# ISRelayV13.net
KiCad netlist of a schematic drawn in EAGLE
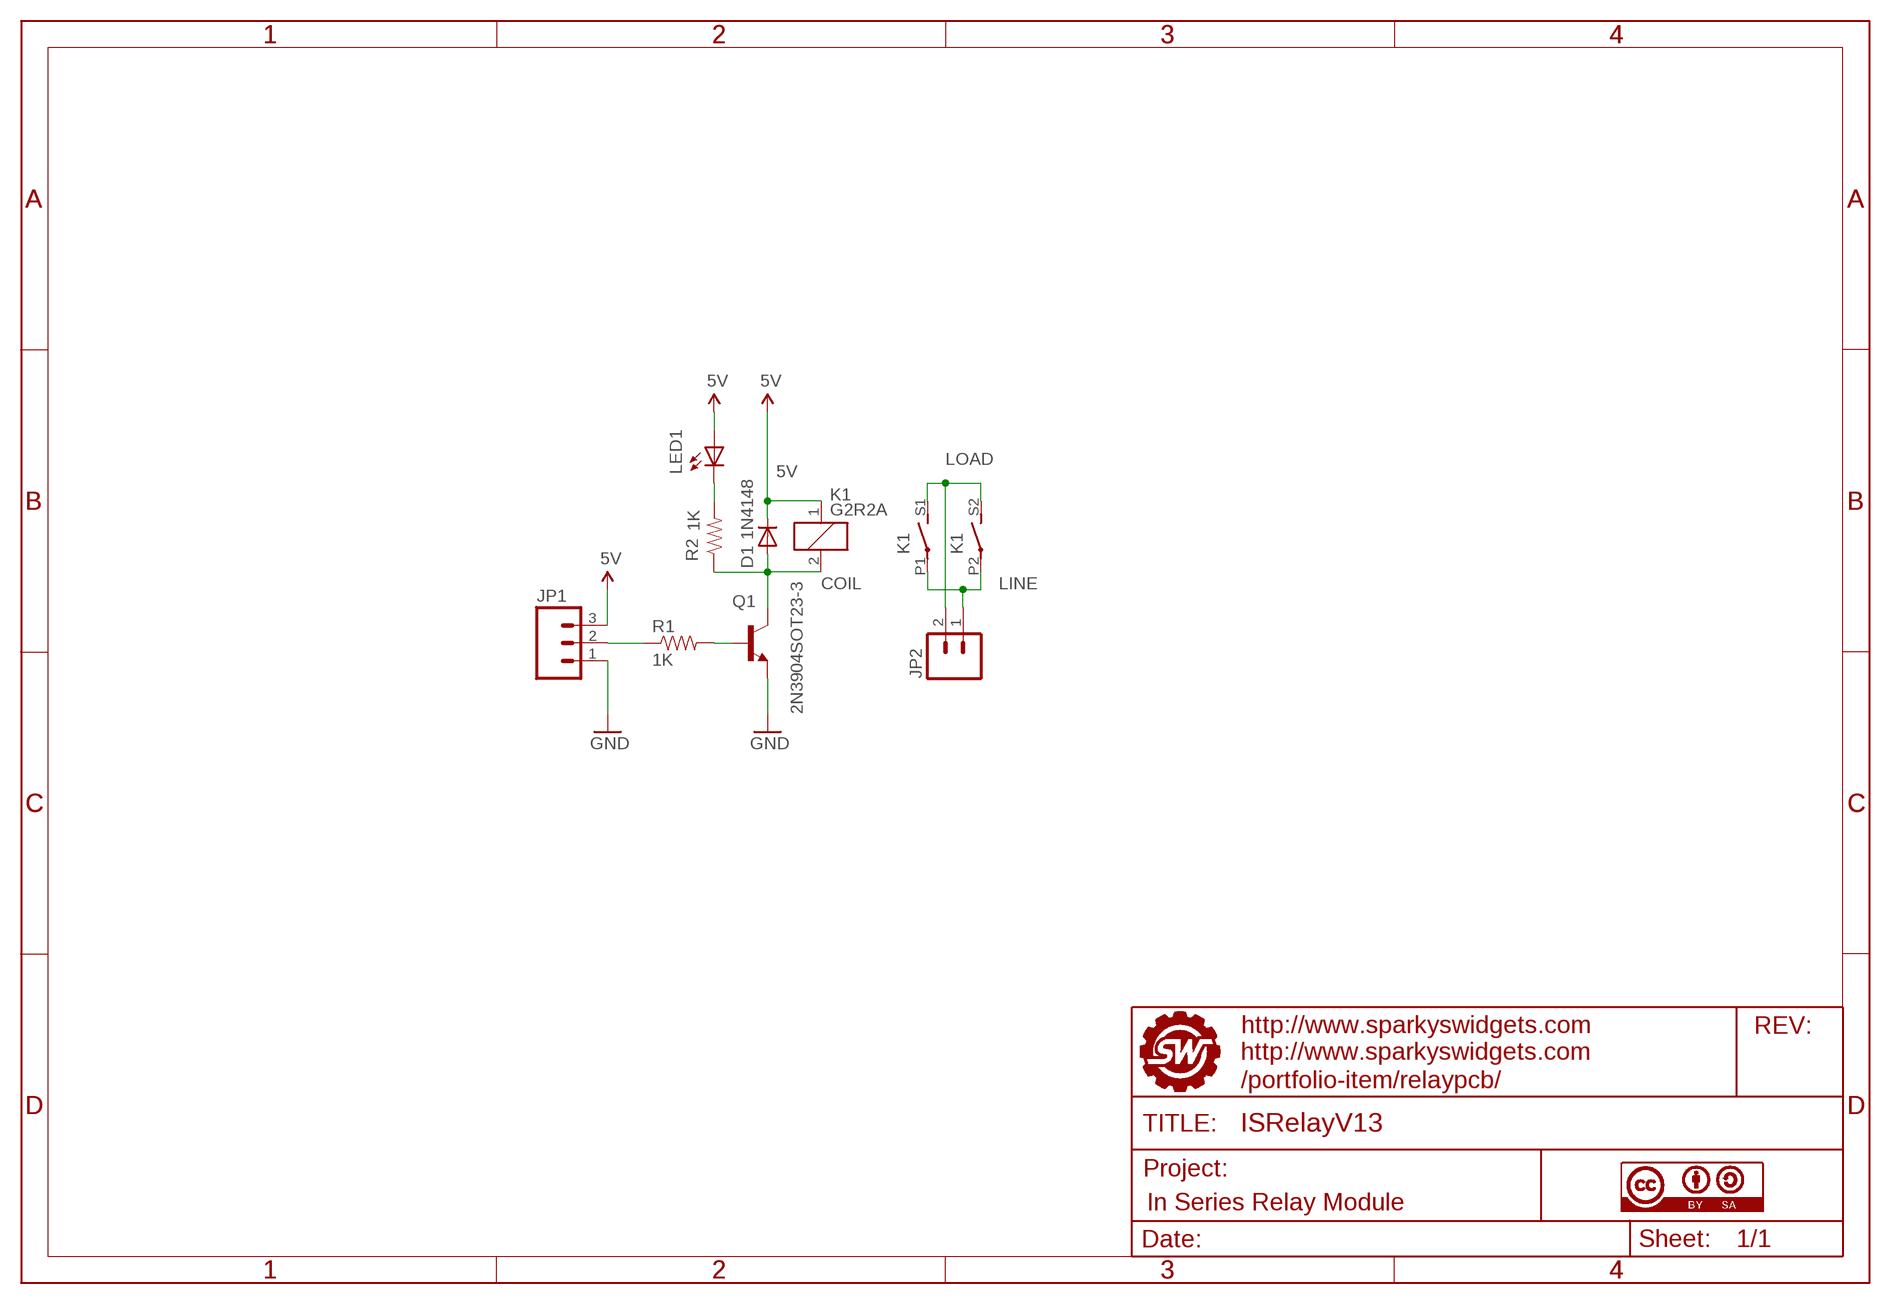
[diagram p0: schematic, sheet 1]

(export (version "E")
  (design (tool "Eeschema 10.0.6"))
  (components
    (comp (ref "D1")
      (value "1N4148")
      (footprint "eagle-import:SOD123")
      (libsource (lib "eagle-import") (part "MBR0520LT"))
    )
    (comp (ref "JP1")
      (value "M03SCREW")
      (footprint "eagle-import:SCREWTERMINAL-3.5MM-3")
      (libsource (lib "eagle-import") (part "M03SCREW"))
    )
    (comp (ref "JP2")
      (value "M025MM")
      (footprint "eagle-import:SCREWTERMINAL-5MM-2")
      (libsource (lib "eagle-import") (part "M025MM"))
    )
    (comp (ref "K1")
      (value "G2R2A")
      (footprint "eagle-import:G2R2A")
      (fields (field (name "MPN") "G2R-2A-DC24"))
      (libsource (lib "eagle-import") (part "G2R2A"))
    )
    (comp (ref "LED1")
      (value "LEDCHIP-LED0805")
      (footprint "eagle-import:CHIP-LED0805")
      (libsource (lib "eagle-import") (part "LEDCHIP-LED0805"))
    )
    (comp (ref "Q1")
      (value "2N3904SOT23-3")
      (footprint "eagle-import:SOT-23")
      (libsource (lib "eagle-import") (part "2N3904SOT23-3"))
    )
    (comp (ref "R1")
      (value "1K")
      (footprint "eagle-import:0805")
      (libsource (lib "eagle-import") (part "RESISTOR0805-RES"))
    )
    (comp (ref "R2")
      (value "1K")
      (footprint "eagle-import:0805")
      (libsource (lib "eagle-import") (part "RESISTOR0805-RES"))
    )
    (comp (ref "U$9")
      (value "FRAME_ISRELAY")
      (footprint "eagle-import:SWPCBLOGOWITHINFO")
      (libsource (lib "eagle-import") (part "FRAME_ISRELAY"))
    )
    (comp (ref "U$12")
      (value "CC-BY-SA")
      (footprint "eagle-import:CC-BY-SA")
      (libsource (lib "eagle-import") (part "CC-BY-SA"))
    )
  )
  (nets
    (net (code "1") (name "/COIL") (class "Default")
      (node (ref "D1") (pin "A") (pinfunction "A_A") (pintype "passive"))
      (node (ref "K1") (pin "2") (pinfunction "2_2") (pintype "passive"))
      (node (ref "Q1") (pin "1") (pinfunction "C_1") (pintype "passive"))
      (node (ref "R2") (pin "1") (pinfunction "1_1") (pintype "passive"))
    )
    (net (code "2") (name "/LINE") (class "Default")
      (node (ref "JP2") (pin "1") (pinfunction "1_1") (pintype "passive"))
      (node (ref "K1") (pin "P1") (pinfunction "P_P1") (pintype "passive"))
      (node (ref "K1") (pin "P2") (pinfunction "P_P2") (pintype "passive"))
    )
    (net (code "3") (name "/LOAD") (class "Default")
      (node (ref "JP2") (pin "2") (pinfunction "2_2") (pintype "passive"))
      (node (ref "K1") (pin "S1") (pinfunction "S_S1") (pintype "passive"))
      (node (ref "K1") (pin "S2") (pinfunction "S_S2") (pintype "passive"))
    )
    (net (code "4") (name "5V") (class "Default")
      (node (ref "D1") (pin "C") (pinfunction "C_C") (pintype "passive"))
      (node (ref "JP1") (pin "3") (pinfunction "3_3") (pintype "passive"))
      (node (ref "K1") (pin "1") (pinfunction "1_1") (pintype "passive"))
      (node (ref "LED1") (pin "A") (pinfunction "A_A") (pintype "passive"))
    )
    (net (code "5") (name "GND") (class "Default")
      (node (ref "JP1") (pin "1") (pinfunction "1_1") (pintype "passive"))
      (node (ref "Q1") (pin "2") (pinfunction "E_2") (pintype "passive"))
    )
    (net (code "6") (name "Net-(JP1-Pad2)") (class "Default")
      (node (ref "JP1") (pin "2") (pinfunction "2_2") (pintype "passive"))
      (node (ref "R1") (pin "1") (pinfunction "1_1") (pintype "passive"))
    )
    (net (code "7") (name "Net-(LED1-PadC)") (class "Default")
      (node (ref "LED1") (pin "C") (pinfunction "C_C") (pintype "passive"))
      (node (ref "R2") (pin "2") (pinfunction "2_2") (pintype "passive"))
    )
    (net (code "8") (name "Net-(Q1-B)") (class "Default")
      (node (ref "Q1") (pin "3") (pinfunction "B_3") (pintype "passive"))
      (node (ref "R1") (pin "2") (pinfunction "2_2") (pintype "passive"))
    )
  )
)
